# ESP32_MOTORS.net
KiCad netlist of a schematic drawn in Altium Designer
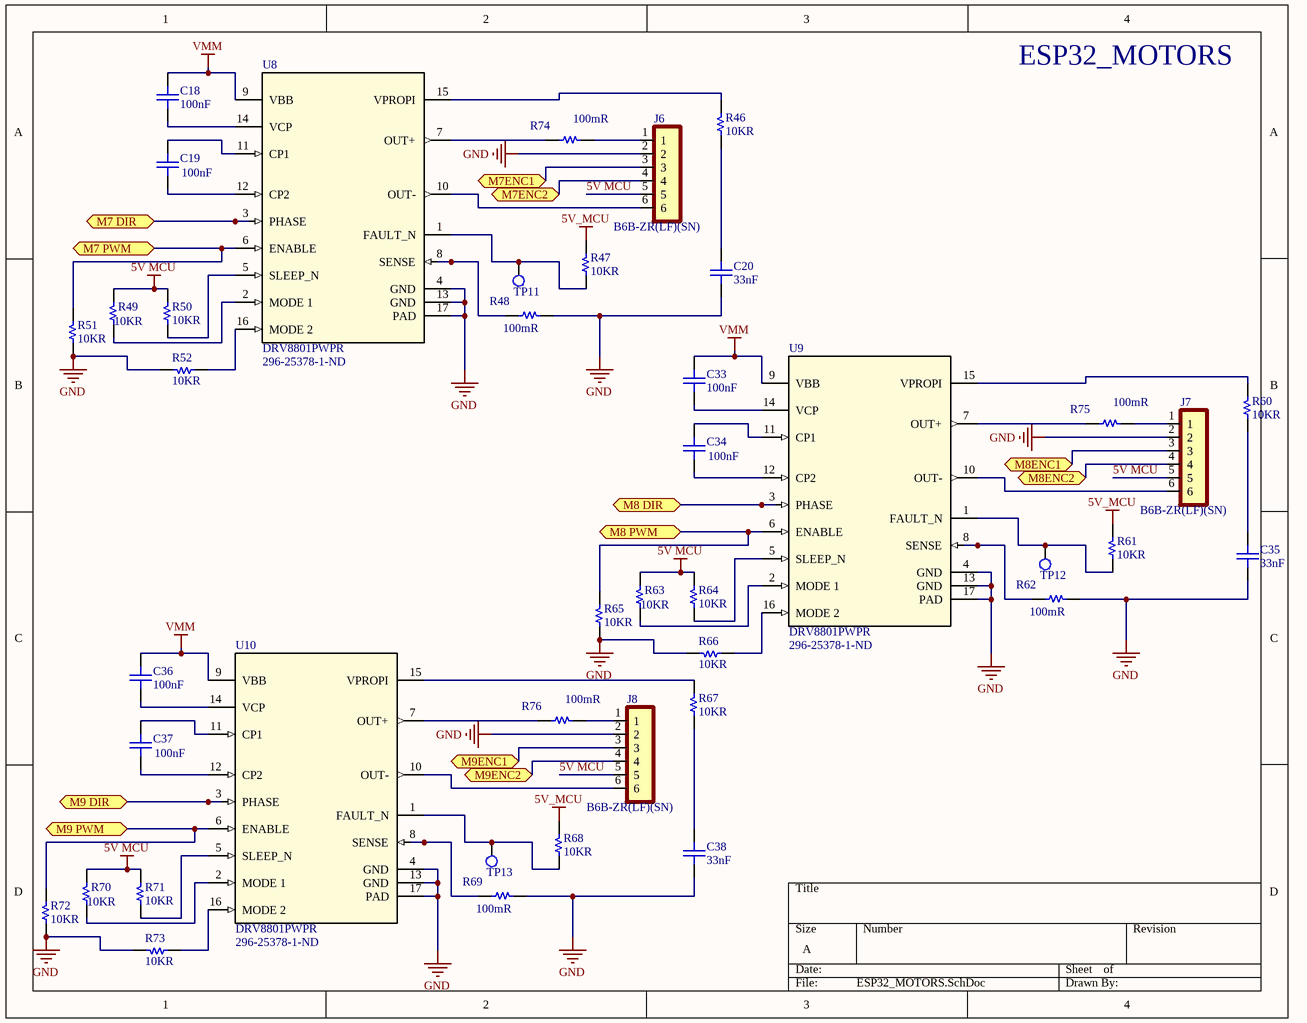
[diagram p0: ESP32_MOTORS.SchDoc]

(export (version "E")
  (design (tool "Eeschema 10.0.6"))
  (components
    (comp (ref "C18")
      (value "100nF")
      (footprint "CAP_ADJ_0805")
      (description "CERAMIC CAPACITOR SMD 0805")
      (fields
        (field (name "MANUFACTURER") "KEMET")
        (field (name "MANUFACTURER PART NUMBER") "C0805C104J5RACAUTO")
      )
      (libsource (lib "ORI_MANIPULATOR_BRD") (part "CAP_ADJ_0805"))
    )
    (comp (ref "C19")
      (value "100nF")
      (footprint "CAP_ADJ_0805")
      (description "CERAMIC CAPACITOR SMD 0805")
      (fields
        (field (name "MANUFACTURER") "KEMET")
        (field (name "MANUFACTURER PART NUMBER") "C0805C104J5RACAUTO")
      )
      (libsource (lib "ORI_MANIPULATOR_BRD") (part "CAP_ADJ_0805"))
    )
    (comp (ref "C20")
      (value "33nF")
      (footprint "CAP_ADJ_0805")
      (description "CERAMIC CAPACITOR SMD 0805")
      (fields
        (field (name "MANUFACTURER") "Samsung")
        (field (name "MANUFACTURER PART NUMBER") "CL21B333JBANNNC")
      )
      (libsource (lib "ORI_MANIPULATOR_BRD") (part "CAP_ADJ_0805"))
    )
    (comp (ref "C33")
      (value "100nF")
      (footprint "CAP_ADJ_0805")
      (description "CERAMIC CAPACITOR SMD 0805")
      (fields
        (field (name "MANUFACTURER") "KEMET")
        (field (name "MANUFACTURER PART NUMBER") "C0805C104J5RACAUTO")
      )
      (libsource (lib "ORI_MANIPULATOR_BRD") (part "CAP_ADJ_0805"))
    )
    (comp (ref "C34")
      (value "100nF")
      (footprint "CAP_ADJ_0805")
      (description "CERAMIC CAPACITOR SMD 0805")
      (fields
        (field (name "MANUFACTURER") "KEMET")
        (field (name "MANUFACTURER PART NUMBER") "C0805C104J5RACAUTO")
      )
      (libsource (lib "ORI_MANIPULATOR_BRD") (part "CAP_ADJ_0805"))
    )
    (comp (ref "C35")
      (value "33nF")
      (footprint "CAP_ADJ_0805")
      (description "CERAMIC CAPACITOR SMD 0805")
      (fields
        (field (name "MANUFACTURER") "Samsung")
        (field (name "MANUFACTURER PART NUMBER") "CL21B333JBANNNC")
      )
      (libsource (lib "ORI_MANIPULATOR_BRD") (part "CAP_ADJ_0805"))
    )
    (comp (ref "C36")
      (value "100nF")
      (footprint "CAP_ADJ_0805")
      (description "CERAMIC CAPACITOR SMD 0805")
      (fields
        (field (name "MANUFACTURER") "KEMET")
        (field (name "MANUFACTURER PART NUMBER") "C0805C104J5RACAUTO")
      )
      (libsource (lib "ORI_MANIPULATOR_BRD") (part "CAP_ADJ_0805"))
    )
    (comp (ref "C37")
      (value "100nF")
      (footprint "CAP_ADJ_0805")
      (description "CERAMIC CAPACITOR SMD 0805")
      (fields
        (field (name "MANUFACTURER") "KEMET")
        (field (name "MANUFACTURER PART NUMBER") "C0805C104J5RACAUTO")
      )
      (libsource (lib "ORI_MANIPULATOR_BRD") (part "CAP_ADJ_0805"))
    )
    (comp (ref "C38")
      (value "33nF")
      (footprint "CAP_ADJ_0805")
      (description "CERAMIC CAPACITOR SMD 0805")
      (fields
        (field (name "MANUFACTURER") "Samsung")
        (field (name "MANUFACTURER PART NUMBER") "CL21B333JBANNNC")
      )
      (libsource (lib "ORI_MANIPULATOR_BRD") (part "CAP_ADJ_0805"))
    )
    (comp (ref "J6")
      (value "B6B-ZR(LF)(SN)")
      (footprint "SnapEDApcb:JST_B6B-ZR(LF)(SN)")
      (description "Connector Header Through Hole 6 position 0.059 _1.50mm_")
      (fields (field (name "MF") "JST Sales") (field (name "MP") "B6B-ZR_LF__SN_"))
      (libsource (lib "SnapEDAsch") (part "B6B-ZR(LF)(SN)"))
    )
    (comp (ref "J7")
      (value "B6B-ZR(LF)(SN)")
      (footprint "SnapEDApcb:JST_B6B-ZR(LF)(SN)")
      (description "Connector Header Through Hole 6 position 0.059 _1.50mm_")
      (fields (field (name "MF") "JST Sales") (field (name "MP") "B6B-ZR_LF__SN_"))
      (libsource (lib "SnapEDAsch") (part "B6B-ZR(LF)(SN)"))
    )
    (comp (ref "J8")
      (value "B6B-ZR(LF)(SN)")
      (footprint "SnapEDApcb:JST_B6B-ZR(LF)(SN)")
      (description "Connector Header Through Hole 6 position 0.059 _1.50mm_")
      (fields (field (name "MF") "JST Sales") (field (name "MP") "B6B-ZR_LF__SN_"))
      (libsource (lib "SnapEDAsch") (part "B6B-ZR(LF)(SN)"))
    )
    (comp (ref "R46")
      (value "10KR")
      (footprint "RES_ADJ_0805_YAGEO")
      (description "RESISTOR 0805 YAGEO")
      (fields
        (field (name "MANUFACTURER") "Yageo")
        (field (name "MANUFACTURER PART NUMBER") "RC0805JR-0710KL")
      )
      (libsource (lib "ORI_MANIPULATOR_BRD") (part "RES_ADJ_0805"))
    )
    (comp (ref "R47")
      (value "10KR")
      (footprint "RES_ADJ_0805_YAGEO")
      (description "RESISTOR 0805 YAGEO")
      (fields
        (field (name "MANUFACTURER") "Yageo")
        (field (name "MANUFACTURER PART NUMBER") "RC0805JR-0710KL")
      )
      (libsource (lib "ORI_MANIPULATOR_BRD") (part "RES_ADJ_0805"))
    )
    (comp (ref "R48")
      (value "100mR")
      (footprint "RES_ADJ_0805_YAGEO")
      (description "RESISTOR 0805 YAGEO")
      (fields
        (field (name "MANUFACTURER") "Panasonic")
        (field (name "MANUFACTURER PART NUMBER") "ERJ-6DSFR10V")
      )
      (libsource (lib "ORI_MANIPULATOR_BRD") (part "RES_ADJ_0805"))
    )
    (comp (ref "R49")
      (value "10KR")
      (footprint "RES_ADJ_0805_YAGEO")
      (description "RESISTOR 0805 YAGEO")
      (fields
        (field (name "MANUFACTURER") "Yageo")
        (field (name "MANUFACTURER PART NUMBER") "RC0805JR-0710KL")
      )
      (libsource (lib "ORI_MANIPULATOR_BRD") (part "RES_ADJ_0805"))
    )
    (comp (ref "R50")
      (value "10KR")
      (footprint "RES_ADJ_0805_YAGEO")
      (description "RESISTOR 0805 YAGEO")
      (fields
        (field (name "MANUFACTURER") "Yageo")
        (field (name "MANUFACTURER PART NUMBER") "RC0805JR-0710KL")
      )
      (libsource (lib "ORI_MANIPULATOR_BRD") (part "RES_ADJ_0805"))
    )
    (comp (ref "R51")
      (value "10KR")
      (footprint "RES_ADJ_0805_YAGEO")
      (description "RESISTOR 0805 YAGEO")
      (fields
        (field (name "MANUFACTURER") "Yageo")
        (field (name "MANUFACTURER PART NUMBER") "RC0805JR-0710KL")
      )
      (libsource (lib "ORI_MANIPULATOR_BRD") (part "RES_ADJ_0805"))
    )
    (comp (ref "R52")
      (value "10KR")
      (footprint "RES_ADJ_0805_YAGEO")
      (description "RESISTOR 0805 YAGEO")
      (fields
        (field (name "MANUFACTURER") "Yageo")
        (field (name "MANUFACTURER PART NUMBER") "RC0805JR-0710KL")
      )
      (libsource (lib "ORI_MANIPULATOR_BRD") (part "RES_ADJ_0805"))
    )
    (comp (ref "R60")
      (value "10KR")
      (footprint "RES_ADJ_0805_YAGEO")
      (description "RESISTOR 0805 YAGEO")
      (fields
        (field (name "MANUFACTURER") "Yageo")
        (field (name "MANUFACTURER PART NUMBER") "RC0805JR-0710KL")
      )
      (libsource (lib "ORI_MANIPULATOR_BRD") (part "RES_ADJ_0805"))
    )
    (comp (ref "R61")
      (value "10KR")
      (footprint "RES_ADJ_0805_YAGEO")
      (description "RESISTOR 0805 YAGEO")
      (fields
        (field (name "MANUFACTURER") "Yageo")
        (field (name "MANUFACTURER PART NUMBER") "RC0805JR-0710KL")
      )
      (libsource (lib "ORI_MANIPULATOR_BRD") (part "RES_ADJ_0805"))
    )
    (comp (ref "R62")
      (value "100mR")
      (footprint "RES_ADJ_0805_YAGEO")
      (description "RESISTOR 0805 YAGEO")
      (fields
        (field (name "MANUFACTURER") "Panasonic")
        (field (name "MANUFACTURER PART NUMBER") "ERJ-6DSFR10V")
      )
      (libsource (lib "ORI_MANIPULATOR_BRD") (part "RES_ADJ_0805"))
    )
    (comp (ref "R63")
      (value "10KR")
      (footprint "RES_ADJ_0805_YAGEO")
      (description "RESISTOR 0805 YAGEO")
      (fields
        (field (name "MANUFACTURER") "Yageo")
        (field (name "MANUFACTURER PART NUMBER") "RC0805JR-0710KL")
      )
      (libsource (lib "ORI_MANIPULATOR_BRD") (part "RES_ADJ_0805"))
    )
    (comp (ref "R64")
      (value "10KR")
      (footprint "RES_ADJ_0805_YAGEO")
      (description "RESISTOR 0805 YAGEO")
      (fields
        (field (name "MANUFACTURER") "Yageo")
        (field (name "MANUFACTURER PART NUMBER") "RC0805JR-0710KL")
      )
      (libsource (lib "ORI_MANIPULATOR_BRD") (part "RES_ADJ_0805"))
    )
    (comp (ref "R65")
      (value "10KR")
      (footprint "RES_ADJ_0805_YAGEO")
      (description "RESISTOR 0805 YAGEO")
      (fields
        (field (name "MANUFACTURER") "Yageo")
        (field (name "MANUFACTURER PART NUMBER") "RC0805JR-0710KL")
      )
      (libsource (lib "ORI_MANIPULATOR_BRD") (part "RES_ADJ_0805"))
    )
    (comp (ref "R66")
      (value "10KR")
      (footprint "RES_ADJ_0805_YAGEO")
      (description "RESISTOR 0805 YAGEO")
      (fields
        (field (name "MANUFACTURER") "Yageo")
        (field (name "MANUFACTURER PART NUMBER") "RC0805JR-0710KL")
      )
      (libsource (lib "ORI_MANIPULATOR_BRD") (part "RES_ADJ_0805"))
    )
    (comp (ref "R67")
      (value "10KR")
      (footprint "RES_ADJ_0805_YAGEO")
      (description "RESISTOR 0805 YAGEO")
      (fields
        (field (name "MANUFACTURER") "Yageo")
        (field (name "MANUFACTURER PART NUMBER") "RC0805JR-0710KL")
      )
      (libsource (lib "ORI_MANIPULATOR_BRD") (part "RES_ADJ_0805"))
    )
    (comp (ref "R68")
      (value "10KR")
      (footprint "RES_ADJ_0805_YAGEO")
      (description "RESISTOR 0805 YAGEO")
      (fields
        (field (name "MANUFACTURER") "Yageo")
        (field (name "MANUFACTURER PART NUMBER") "RC0805JR-0710KL")
      )
      (libsource (lib "ORI_MANIPULATOR_BRD") (part "RES_ADJ_0805"))
    )
    (comp (ref "R69")
      (value "100mR")
      (footprint "RES_ADJ_0805_YAGEO")
      (description "RESISTOR 0805 YAGEO")
      (fields
        (field (name "MANUFACTURER") "Panasonic")
        (field (name "MANUFACTURER PART NUMBER") "ERJ-6DSFR10V")
      )
      (libsource (lib "ORI_MANIPULATOR_BRD") (part "RES_ADJ_0805"))
    )
    (comp (ref "R70")
      (value "10KR")
      (footprint "RES_ADJ_0805_YAGEO")
      (description "RESISTOR 0805 YAGEO")
      (fields
        (field (name "MANUFACTURER") "Yageo")
        (field (name "MANUFACTURER PART NUMBER") "RC0805JR-0710KL")
      )
      (libsource (lib "ORI_MANIPULATOR_BRD") (part "RES_ADJ_0805"))
    )
    (comp (ref "R71")
      (value "10KR")
      (footprint "RES_ADJ_0805_YAGEO")
      (description "RESISTOR 0805 YAGEO")
      (fields
        (field (name "MANUFACTURER") "Yageo")
        (field (name "MANUFACTURER PART NUMBER") "RC0805JR-0710KL")
      )
      (libsource (lib "ORI_MANIPULATOR_BRD") (part "RES_ADJ_0805"))
    )
    (comp (ref "R72")
      (value "10KR")
      (footprint "RES_ADJ_0805_YAGEO")
      (description "RESISTOR 0805 YAGEO")
      (fields
        (field (name "MANUFACTURER") "Yageo")
        (field (name "MANUFACTURER PART NUMBER") "RC0805JR-0710KL")
      )
      (libsource (lib "ORI_MANIPULATOR_BRD") (part "RES_ADJ_0805"))
    )
    (comp (ref "R73")
      (value "10KR")
      (footprint "RES_ADJ_0805_YAGEO")
      (description "RESISTOR 0805 YAGEO")
      (fields
        (field (name "MANUFACTURER") "Yageo")
        (field (name "MANUFACTURER PART NUMBER") "RC0805JR-0710KL")
      )
      (libsource (lib "ORI_MANIPULATOR_BRD") (part "RES_ADJ_0805"))
    )
    (comp (ref "R74")
      (value "100mR")
      (footprint "RES_ADJ_0805_YAGEO")
      (description "RESISTOR 0805 YAGEO")
      (fields
        (field (name "MANUFACTURER") "Panasonic")
        (field (name "MANUFACTURER PART NUMBER") "ERJ-6DSFR10V")
      )
      (libsource (lib "ORI_MANIPULATOR_BRD") (part "RES_ADJ_0805"))
    )
    (comp (ref "R75")
      (value "100mR")
      (footprint "RES_ADJ_0805_YAGEO")
      (description "RESISTOR 0805 YAGEO")
      (fields
        (field (name "MANUFACTURER") "Panasonic")
        (field (name "MANUFACTURER PART NUMBER") "ERJ-6DSFR10V")
      )
      (libsource (lib "ORI_MANIPULATOR_BRD") (part "RES_ADJ_0805"))
    )
    (comp (ref "R76")
      (value "100mR")
      (footprint "RES_ADJ_0805_YAGEO")
      (description "RESISTOR 0805 YAGEO")
      (fields
        (field (name "MANUFACTURER") "Panasonic")
        (field (name "MANUFACTURER PART NUMBER") "ERJ-6DSFR10V")
      )
      (libsource (lib "ORI_MANIPULATOR_BRD") (part "RES_ADJ_0805"))
    )
    (comp (ref "TP11")
      (value "TEST_POINT")
      (footprint "TEST_POINT")
      (description "TEST POINT PAD")
      (libsource (lib "ORI_MANIPULATOR_BRD") (part "TEST_POINT"))
    )
    (comp (ref "TP12")
      (value "TEST_POINT")
      (footprint "TEST_POINT")
      (description "TEST POINT PAD")
      (libsource (lib "ORI_MANIPULATOR_BRD") (part "TEST_POINT"))
    )
    (comp (ref "TP13")
      (value "TEST_POINT")
      (footprint "TEST_POINT")
      (description "TEST POINT PAD")
      (libsource (lib "ORI_MANIPULATOR_BRD") (part "TEST_POINT"))
    )
    (comp (ref "U8")
      (value "DRV8801PWPR")
      (footprint "PWP0016B_N")
      (description "IC MOTOR DRIVER PAR 16HTSSOP")
      (fields
        (field (name "MANUFACTURER") "Texas Instruments")
        (field (name "SUPPLIER PART NUMBER 1") "296-25378-1-ND")
      )
      (libsource (lib "ORI_MANIPULATOR_BRD") (part "DRV8801PWPR"))
    )
    (comp (ref "U9")
      (value "DRV8801PWPR")
      (footprint "PWP0016B_N")
      (description "IC MOTOR DRIVER PAR 16HTSSOP")
      (fields
        (field (name "MANUFACTURER") "Texas Instruments")
        (field (name "SUPPLIER PART NUMBER 1") "296-25378-1-ND")
      )
      (libsource (lib "ORI_MANIPULATOR_BRD") (part "DRV8801PWPR"))
    )
    (comp (ref "U10")
      (value "DRV8801PWPR")
      (footprint "PWP0016B_N")
      (description "IC MOTOR DRIVER PAR 16HTSSOP")
      (fields
        (field (name "MANUFACTURER") "Texas Instruments")
        (field (name "SUPPLIER PART NUMBER 1") "296-25378-1-ND")
      )
      (libsource (lib "ORI_MANIPULATOR_BRD") (part "DRV8801PWPR"))
    )
  )
  (nets
    (net (code "1") (name "/M7 DIR") (class "Default")
      (node (ref "U8") (pin "3") (pinfunction "PHASE_3") (pintype "input"))
    )
    (net (code "2") (name "/M7 PWM") (class "Default")
      (node (ref "R51") (pin "2") (pinfunction "2_2") (pintype "passive"))
      (node (ref "U8") (pin "6") (pinfunction "ENABLE_6") (pintype "input"))
    )
    (net (code "3") (name "/M7ENC1") (class "Default")
      (node (ref "J6") (pin "3") (pinfunction "3_3") (pintype "passive"))
    )
    (net (code "4") (name "/M7ENC2") (class "Default")
      (node (ref "J6") (pin "4") (pinfunction "4_4") (pintype "passive"))
    )
    (net (code "5") (name "/M8 DIR") (class "Default")
      (node (ref "U9") (pin "3") (pinfunction "PHASE_3") (pintype "input"))
    )
    (net (code "6") (name "/M8 PWM") (class "Default")
      (node (ref "R65") (pin "2") (pinfunction "2_2") (pintype "passive"))
      (node (ref "U9") (pin "6") (pinfunction "ENABLE_6") (pintype "input"))
    )
    (net (code "7") (name "/M8ENC1") (class "Default")
      (node (ref "J7") (pin "3") (pinfunction "3_3") (pintype "passive"))
    )
    (net (code "8") (name "/M8ENC2") (class "Default")
      (node (ref "J7") (pin "4") (pinfunction "4_4") (pintype "passive"))
    )
    (net (code "9") (name "/M9 DIR") (class "Default")
      (node (ref "U10") (pin "3") (pinfunction "PHASE_3") (pintype "input"))
    )
    (net (code "10") (name "/M9 PWM") (class "Default")
      (node (ref "R72") (pin "2") (pinfunction "2_2") (pintype "passive"))
      (node (ref "U10") (pin "6") (pinfunction "ENABLE_6") (pintype "input"))
    )
    (net (code "11") (name "/M9ENC1") (class "Default")
      (node (ref "J8") (pin "3") (pinfunction "3_3") (pintype "passive"))
    )
    (net (code "12") (name "/M9ENC2") (class "Default")
      (node (ref "J8") (pin "4") (pinfunction "4_4") (pintype "passive"))
    )
    (net (code "13") (name "5V MCU") (class "Default")
      (node (ref "J6") (pin "5") (pinfunction "5_5") (pintype "passive"))
      (node (ref "J7") (pin "5") (pinfunction "5_5") (pintype "passive"))
      (node (ref "J8") (pin "5") (pinfunction "5_5") (pintype "passive"))
      (node (ref "R49") (pin "2") (pinfunction "2_2") (pintype "passive"))
      (node (ref "R50") (pin "2") (pinfunction "2_2") (pintype "passive"))
      (node (ref "R63") (pin "2") (pinfunction "2_2") (pintype "passive"))
      (node (ref "R64") (pin "2") (pinfunction "2_2") (pintype "passive"))
      (node (ref "R70") (pin "2") (pinfunction "2_2") (pintype "passive"))
      (node (ref "R71") (pin "2") (pinfunction "2_2") (pintype "passive"))
    )
    (net (code "14") (name "5V_MCU") (class "Default")
      (node (ref "R47") (pin "2") (pinfunction "2_2") (pintype "passive"))
      (node (ref "R61") (pin "2") (pinfunction "2_2") (pintype "passive"))
      (node (ref "R68") (pin "2") (pinfunction "2_2") (pintype "passive"))
    )
    (net (code "15") (name "GND") (class "Default")
      (node (ref "C20") (pin "1") (pinfunction "1_1") (pintype "passive"))
      (node (ref "C35") (pin "1") (pinfunction "1_1") (pintype "passive"))
      (node (ref "C38") (pin "1") (pinfunction "1_1") (pintype "passive"))
      (node (ref "J6") (pin "2") (pinfunction "2_2") (pintype "passive"))
      (node (ref "J7") (pin "2") (pinfunction "2_2") (pintype "passive"))
      (node (ref "J8") (pin "2") (pinfunction "2_2") (pintype "passive"))
      (node (ref "R48") (pin "2") (pinfunction "2_2") (pintype "passive"))
      (node (ref "R51") (pin "1") (pinfunction "1_1") (pintype "passive"))
      (node (ref "R52") (pin "2") (pinfunction "2_2") (pintype "passive"))
      (node (ref "R62") (pin "2") (pinfunction "2_2") (pintype "passive"))
      (node (ref "R65") (pin "1") (pinfunction "1_1") (pintype "passive"))
      (node (ref "R66") (pin "2") (pinfunction "2_2") (pintype "passive"))
      (node (ref "R69") (pin "2") (pinfunction "2_2") (pintype "passive"))
      (node (ref "R72") (pin "1") (pinfunction "1_1") (pintype "passive"))
      (node (ref "R73") (pin "2") (pinfunction "2_2") (pintype "passive"))
      (node (ref "U10") (pin "13") (pinfunction "GND_13") (pintype "power_in"))
      (node (ref "U10") (pin "17") (pinfunction "PAD_17") (pintype "power_in"))
      (node (ref "U10") (pin "4") (pinfunction "GND_4") (pintype "power_in"))
      (node (ref "U8") (pin "13") (pinfunction "GND_13") (pintype "power_in"))
      (node (ref "U8") (pin "17") (pinfunction "PAD_17") (pintype "power_in"))
      (node (ref "U8") (pin "4") (pinfunction "GND_4") (pintype "power_in"))
      (node (ref "U9") (pin "13") (pinfunction "GND_13") (pintype "power_in"))
      (node (ref "U9") (pin "17") (pinfunction "PAD_17") (pintype "power_in"))
      (node (ref "U9") (pin "4") (pinfunction "GND_4") (pintype "power_in"))
    )
    (net (code "16") (name "Net-(C20-Pad2)") (class "Default")
      (node (ref "C20") (pin "2") (pinfunction "2_2") (pintype "passive"))
      (node (ref "R46") (pin "1") (pinfunction "1_1") (pintype "passive"))
    )
    (net (code "17") (name "Net-(C35-Pad2)") (class "Default")
      (node (ref "C35") (pin "2") (pinfunction "2_2") (pintype "passive"))
      (node (ref "R60") (pin "1") (pinfunction "1_1") (pintype "passive"))
    )
    (net (code "18") (name "Net-(C38-Pad2)") (class "Default")
      (node (ref "C38") (pin "2") (pinfunction "2_2") (pintype "passive"))
      (node (ref "R67") (pin "1") (pinfunction "1_1") (pintype "passive"))
    )
    (net (code "19") (name "Net-(J6-Pad1)") (class "Default")
      (node (ref "J6") (pin "1") (pinfunction "1_1") (pintype "passive"))
      (node (ref "R74") (pin "2") (pinfunction "2_2") (pintype "passive"))
    )
    (net (code "20") (name "Net-(J7-Pad1)") (class "Default")
      (node (ref "J7") (pin "1") (pinfunction "1_1") (pintype "passive"))
      (node (ref "R75") (pin "2") (pinfunction "2_2") (pintype "passive"))
    )
    (net (code "21") (name "Net-(J8-Pad1)") (class "Default")
      (node (ref "J8") (pin "1") (pinfunction "1_1") (pintype "passive"))
      (node (ref "R76") (pin "2") (pinfunction "2_2") (pintype "passive"))
    )
    (net (code "22") (name "Net-(U8-CP1)") (class "Default")
      (node (ref "C19") (pin "2") (pinfunction "2_2") (pintype "passive"))
      (node (ref "U8") (pin "11") (pinfunction "CP1_11") (pintype "input"))
    )
    (net (code "23") (name "Net-(U8-CP2)") (class "Default")
      (node (ref "C19") (pin "1") (pinfunction "1_1") (pintype "passive"))
      (node (ref "U8") (pin "12") (pinfunction "CP2_12") (pintype "input"))
    )
    (net (code "24") (name "Net-(U8-FAULT_N)") (class "Default")
      (node (ref "R47") (pin "1") (pinfunction "1_1") (pintype "passive"))
      (node (ref "TP11") (pin "1") (pinfunction "1_1") (pintype "passive"))
      (node (ref "U8") (pin "1") (pinfunction "FAULT_N_1") (pintype "open_collector"))
    )
    (net (code "25") (name "Net-(U8-MODE_1)") (class "Default")
      (node (ref "R49") (pin "1") (pinfunction "1_1") (pintype "passive"))
      (node (ref "U8") (pin "2") (pinfunction "MODE_1_2") (pintype "input"))
    )
    (net (code "26") (name "Net-(U8-MODE_2)") (class "Default")
      (node (ref "R52") (pin "1") (pinfunction "1_1") (pintype "passive"))
      (node (ref "U8") (pin "16") (pinfunction "MODE_2_16") (pintype "input"))
    )
    (net (code "27") (name "Net-(U8-OUT+)") (class "Default")
      (node (ref "R74") (pin "1") (pinfunction "1_1") (pintype "passive"))
      (node (ref "U8") (pin "7") (pinfunction "OUT+_7") (pintype "output"))
    )
    (net (code "28") (name "Net-(U8-OUT-)") (class "Default")
      (node (ref "J6") (pin "6") (pinfunction "6_6") (pintype "passive"))
      (node (ref "U8") (pin "10") (pinfunction "OUT-_10") (pintype "output"))
    )
    (net (code "29") (name "Net-(U8-SENSE)") (class "Default")
      (node (ref "R48") (pin "1") (pinfunction "1_1") (pintype "passive"))
      (node (ref "U8") (pin "8") (pinfunction "SENSE_8") (pintype "input"))
    )
    (net (code "30") (name "Net-(U8-SLEEP_N)") (class "Default")
      (node (ref "R50") (pin "1") (pinfunction "1_1") (pintype "passive"))
      (node (ref "U8") (pin "5") (pinfunction "SLEEP_N_5") (pintype "input"))
    )
    (net (code "31") (name "Net-(U8-VCP)") (class "Default")
      (node (ref "C18") (pin "1") (pinfunction "1_1") (pintype "passive"))
      (node (ref "U8") (pin "14") (pinfunction "VCP_14") (pintype "passive"))
    )
    (net (code "32") (name "Net-(U8-VPROPI)") (class "Default")
      (node (ref "R46") (pin "2") (pinfunction "2_2") (pintype "passive"))
      (node (ref "U8") (pin "15") (pinfunction "VPROPI_15") (pintype "power_in"))
    )
    (net (code "33") (name "Net-(U9-CP1)") (class "Default")
      (node (ref "C34") (pin "2") (pinfunction "2_2") (pintype "passive"))
      (node (ref "U9") (pin "11") (pinfunction "CP1_11") (pintype "input"))
    )
    (net (code "34") (name "Net-(U9-CP2)") (class "Default")
      (node (ref "C34") (pin "1") (pinfunction "1_1") (pintype "passive"))
      (node (ref "U9") (pin "12") (pinfunction "CP2_12") (pintype "input"))
    )
    (net (code "35") (name "Net-(U9-FAULT_N)") (class "Default")
      (node (ref "R61") (pin "1") (pinfunction "1_1") (pintype "passive"))
      (node (ref "TP12") (pin "1") (pinfunction "1_1") (pintype "passive"))
      (node (ref "U9") (pin "1") (pinfunction "FAULT_N_1") (pintype "open_collector"))
    )
    (net (code "36") (name "Net-(U9-MODE_1)") (class "Default")
      (node (ref "R63") (pin "1") (pinfunction "1_1") (pintype "passive"))
      (node (ref "U9") (pin "2") (pinfunction "MODE_1_2") (pintype "input"))
    )
    (net (code "37") (name "Net-(U9-MODE_2)") (class "Default")
      (node (ref "R66") (pin "1") (pinfunction "1_1") (pintype "passive"))
      (node (ref "U9") (pin "16") (pinfunction "MODE_2_16") (pintype "input"))
    )
    (net (code "38") (name "Net-(U9-OUT+)") (class "Default")
      (node (ref "R75") (pin "1") (pinfunction "1_1") (pintype "passive"))
      (node (ref "U9") (pin "7") (pinfunction "OUT+_7") (pintype "output"))
    )
    (net (code "39") (name "Net-(U9-OUT-)") (class "Default")
      (node (ref "J7") (pin "6") (pinfunction "6_6") (pintype "passive"))
      (node (ref "U9") (pin "10") (pinfunction "OUT-_10") (pintype "output"))
    )
    (net (code "40") (name "Net-(U9-SENSE)") (class "Default")
      (node (ref "R62") (pin "1") (pinfunction "1_1") (pintype "passive"))
      (node (ref "U9") (pin "8") (pinfunction "SENSE_8") (pintype "input"))
    )
    (net (code "41") (name "Net-(U9-SLEEP_N)") (class "Default")
      (node (ref "R64") (pin "1") (pinfunction "1_1") (pintype "passive"))
      (node (ref "U9") (pin "5") (pinfunction "SLEEP_N_5") (pintype "input"))
    )
    (net (code "42") (name "Net-(U9-VCP)") (class "Default")
      (node (ref "C33") (pin "1") (pinfunction "1_1") (pintype "passive"))
      (node (ref "U9") (pin "14") (pinfunction "VCP_14") (pintype "passive"))
    )
    (net (code "43") (name "Net-(U9-VPROPI)") (class "Default")
      (node (ref "R60") (pin "2") (pinfunction "2_2") (pintype "passive"))
      (node (ref "U9") (pin "15") (pinfunction "VPROPI_15") (pintype "power_in"))
    )
    (net (code "44") (name "Net-(U10-CP1)") (class "Default")
      (node (ref "C37") (pin "2") (pinfunction "2_2") (pintype "passive"))
      (node (ref "U10") (pin "11") (pinfunction "CP1_11") (pintype "input"))
    )
    (net (code "45") (name "Net-(U10-CP2)") (class "Default")
      (node (ref "C37") (pin "1") (pinfunction "1_1") (pintype "passive"))
      (node (ref "U10") (pin "12") (pinfunction "CP2_12") (pintype "input"))
    )
    (net (code "46") (name "Net-(U10-FAULT_N)") (class "Default")
      (node (ref "R68") (pin "1") (pinfunction "1_1") (pintype "passive"))
      (node (ref "TP13") (pin "1") (pinfunction "1_1") (pintype "passive"))
      (node (ref "U10") (pin "1") (pinfunction "FAULT_N_1") (pintype "open_collector"))
    )
    (net (code "47") (name "Net-(U10-MODE_1)") (class "Default")
      (node (ref "R70") (pin "1") (pinfunction "1_1") (pintype "passive"))
      (node (ref "U10") (pin "2") (pinfunction "MODE_1_2") (pintype "input"))
    )
    (net (code "48") (name "Net-(U10-MODE_2)") (class "Default")
      (node (ref "R73") (pin "1") (pinfunction "1_1") (pintype "passive"))
      (node (ref "U10") (pin "16") (pinfunction "MODE_2_16") (pintype "input"))
    )
    (net (code "49") (name "Net-(U10-OUT+)") (class "Default")
      (node (ref "R76") (pin "1") (pinfunction "1_1") (pintype "passive"))
      (node (ref "U10") (pin "7") (pinfunction "OUT+_7") (pintype "output"))
    )
    (net (code "50") (name "Net-(U10-OUT-)") (class "Default")
      (node (ref "J8") (pin "6") (pinfunction "6_6") (pintype "passive"))
      (node (ref "U10") (pin "10") (pinfunction "OUT-_10") (pintype "output"))
    )
    (net (code "51") (name "Net-(U10-SENSE)") (class "Default")
      (node (ref "R69") (pin "1") (pinfunction "1_1") (pintype "passive"))
      (node (ref "U10") (pin "8") (pinfunction "SENSE_8") (pintype "input"))
    )
    (net (code "52") (name "Net-(U10-SLEEP_N)") (class "Default")
      (node (ref "R71") (pin "1") (pinfunction "1_1") (pintype "passive"))
      (node (ref "U10") (pin "5") (pinfunction "SLEEP_N_5") (pintype "input"))
    )
    (net (code "53") (name "Net-(U10-VCP)") (class "Default")
      (node (ref "C36") (pin "1") (pinfunction "1_1") (pintype "passive"))
      (node (ref "U10") (pin "14") (pinfunction "VCP_14") (pintype "passive"))
    )
    (net (code "54") (name "Net-(U10-VPROPI)") (class "Default")
      (node (ref "R67") (pin "2") (pinfunction "2_2") (pintype "passive"))
      (node (ref "U10") (pin "15") (pinfunction "VPROPI_15") (pintype "power_in"))
    )
    (net (code "55") (name "VMM") (class "Default")
      (node (ref "C18") (pin "2") (pinfunction "2_2") (pintype "passive"))
      (node (ref "C33") (pin "2") (pinfunction "2_2") (pintype "passive"))
      (node (ref "C36") (pin "2") (pinfunction "2_2") (pintype "passive"))
      (node (ref "U10") (pin "9") (pinfunction "VBB_9") (pintype "power_in"))
      (node (ref "U8") (pin "9") (pinfunction "VBB_9") (pintype "power_in"))
      (node (ref "U9") (pin "9") (pinfunction "VBB_9") (pintype "power_in"))
    )
  )
)
